# LED_7SEG.net
KiCad netlist of a schematic drawn in Altium Designer
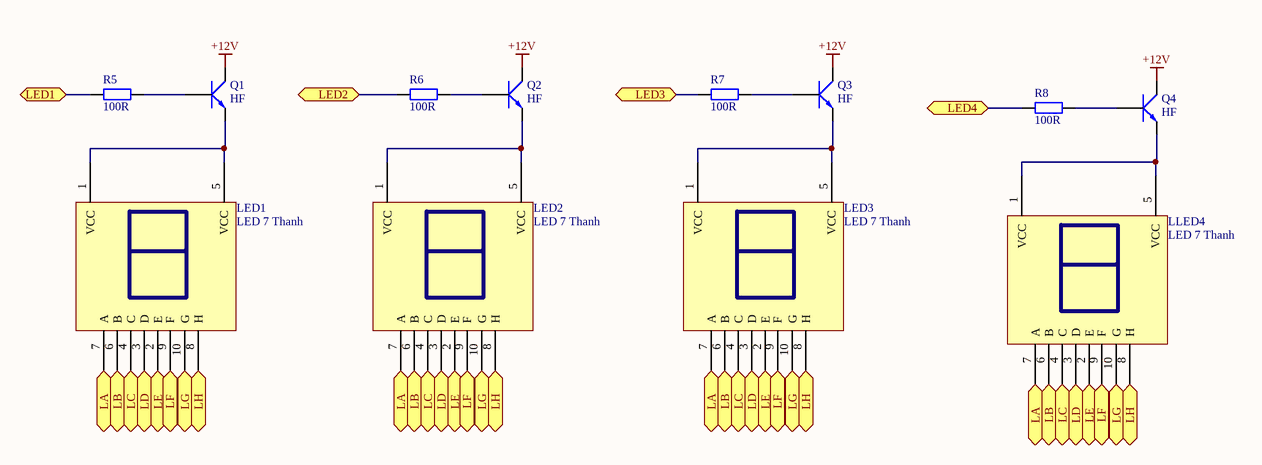
[diagram p0: LED_7SEG.SchDoc]

(export (version "E")
  (design (tool "Eeschema 10.0.6"))
  (components
    (comp (ref "LED1")
      (value "LED 7 Thanh")
      (footprint "LED7SEG_2.3inch")
      (description "Dán")
      (libsource (lib "Altium_Lib_by_KhueNguyenCreator") (part "LED 7x1 2.3inch Anot"))
    )
    (comp (ref "LED2")
      (value "LED 7 Thanh")
      (footprint "LED7SEG_2.3inch")
      (description "Dán")
      (libsource (lib "Altium_Lib_by_KhueNguyenCreator") (part "LED 7x1 2.3inch Anot"))
    )
    (comp (ref "LED3")
      (value "LED 7 Thanh")
      (footprint "LED7SEG_2.3inch")
      (description "Dán")
      (libsource (lib "Altium_Lib_by_KhueNguyenCreator") (part "LED 7x1 2.3inch Anot"))
    )
    (comp (ref "LLED4")
      (value "LED 7 Thanh")
      (footprint "LED7SEG_2.3inch")
      (description "Dán")
      (libsource (lib "Altium_Lib_by_KhueNguyenCreator") (part "LED 7x1 2.3inch Anot"))
    )
    (comp (ref "Q1")
      (value "HF")
      (footprint "SOT23")
      (description "NPN transistor")
      (libsource (lib "Altium_Lib_by_KhueNguyenCreator") (part "C1815 HF SMD"))
    )
    (comp (ref "Q2")
      (value "HF")
      (footprint "SOT23")
      (description "NPN transistor")
      (libsource (lib "Altium_Lib_by_KhueNguyenCreator") (part "C1815 HF SMD"))
    )
    (comp (ref "Q3")
      (value "HF")
      (footprint "SOT23")
      (description "NPN transistor")
      (libsource (lib "Altium_Lib_by_KhueNguyenCreator") (part "C1815 HF SMD"))
    )
    (comp (ref "Q4")
      (value "HF")
      (footprint "SOT23")
      (description "NPN transistor")
      (libsource (lib "Altium_Lib_by_KhueNguyenCreator") (part "C1815 HF SMD"))
    )
    (comp (ref "R5")
      (value "100R")
      (footprint "tro smd 0603")
      (description "Dán")
      (libsource (lib "Altium_Lib_by_KhueNguyenCreator") (part "Tro 0603 5% 100R"))
    )
    (comp (ref "R6")
      (value "100R")
      (footprint "tro smd 0603")
      (description "Dán")
      (libsource (lib "Altium_Lib_by_KhueNguyenCreator") (part "Tro 0603 5% 100R"))
    )
    (comp (ref "R7")
      (value "100R")
      (footprint "tro smd 0603")
      (description "Dán")
      (libsource (lib "Altium_Lib_by_KhueNguyenCreator") (part "Tro 0603 5% 100R"))
    )
    (comp (ref "R8")
      (value "100R")
      (footprint "tro smd 0603")
      (description "Dán")
      (libsource (lib "Altium_Lib_by_KhueNguyenCreator") (part "Tro 0603 5% 100R"))
    )
  )
  (nets
    (net (code "1") (name "+12V") (class "Default")
      (node (ref "Q1") (pin "3") (pinfunction "C_3") (pintype "passive"))
      (node (ref "Q2") (pin "3") (pinfunction "C_3") (pintype "passive"))
      (node (ref "Q3") (pin "3") (pinfunction "C_3") (pintype "passive"))
      (node (ref "Q4") (pin "3") (pinfunction "C_3") (pintype "passive"))
    )
    (net (code "2") (name "/LA") (class "Default")
      (node (ref "LED1") (pin "7") (pinfunction "A_7") (pintype "passive"))
      (node (ref "LED2") (pin "7") (pinfunction "A_7") (pintype "passive"))
      (node (ref "LED3") (pin "7") (pinfunction "A_7") (pintype "passive"))
      (node (ref "LLED4") (pin "7") (pinfunction "A_7") (pintype "passive"))
    )
    (net (code "3") (name "/LB") (class "Default")
      (node (ref "LED1") (pin "6") (pinfunction "B_6") (pintype "passive"))
      (node (ref "LED2") (pin "6") (pinfunction "B_6") (pintype "passive"))
      (node (ref "LED3") (pin "6") (pinfunction "B_6") (pintype "passive"))
      (node (ref "LLED4") (pin "6") (pinfunction "B_6") (pintype "passive"))
    )
    (net (code "4") (name "/LC") (class "Default")
      (node (ref "LED1") (pin "4") (pinfunction "C_4") (pintype "passive"))
      (node (ref "LED2") (pin "4") (pinfunction "C_4") (pintype "passive"))
      (node (ref "LED3") (pin "4") (pinfunction "C_4") (pintype "passive"))
      (node (ref "LLED4") (pin "4") (pinfunction "C_4") (pintype "passive"))
    )
    (net (code "5") (name "/LD") (class "Default")
      (node (ref "LED1") (pin "3") (pinfunction "D_3") (pintype "passive"))
      (node (ref "LED2") (pin "3") (pinfunction "D_3") (pintype "passive"))
      (node (ref "LED3") (pin "3") (pinfunction "D_3") (pintype "passive"))
      (node (ref "LLED4") (pin "3") (pinfunction "D_3") (pintype "passive"))
    )
    (net (code "6") (name "/LE") (class "Default")
      (node (ref "LED1") (pin "2") (pinfunction "E_2") (pintype "passive"))
      (node (ref "LED2") (pin "2") (pinfunction "E_2") (pintype "passive"))
      (node (ref "LED3") (pin "2") (pinfunction "E_2") (pintype "passive"))
      (node (ref "LLED4") (pin "2") (pinfunction "E_2") (pintype "passive"))
    )
    (net (code "7") (name "/LED1") (class "Default")
      (node (ref "R5") (pin "1") (pinfunction "1_1") (pintype "passive"))
    )
    (net (code "8") (name "/LED2") (class "Default")
      (node (ref "R6") (pin "1") (pinfunction "1_1") (pintype "passive"))
    )
    (net (code "9") (name "/LED3") (class "Default")
      (node (ref "R7") (pin "1") (pinfunction "1_1") (pintype "passive"))
    )
    (net (code "10") (name "/LED4") (class "Default")
      (node (ref "R8") (pin "1") (pinfunction "1_1") (pintype "passive"))
    )
    (net (code "11") (name "/LF") (class "Default")
      (node (ref "LED1") (pin "9") (pinfunction "F_9") (pintype "passive"))
      (node (ref "LED2") (pin "9") (pinfunction "F_9") (pintype "passive"))
      (node (ref "LED3") (pin "9") (pinfunction "F_9") (pintype "passive"))
      (node (ref "LLED4") (pin "9") (pinfunction "F_9") (pintype "passive"))
    )
    (net (code "12") (name "/LG") (class "Default")
      (node (ref "LED1") (pin "10") (pinfunction "G_10") (pintype "passive"))
      (node (ref "LED2") (pin "10") (pinfunction "G_10") (pintype "passive"))
      (node (ref "LED3") (pin "10") (pinfunction "G_10") (pintype "passive"))
      (node (ref "LLED4") (pin "10") (pinfunction "G_10") (pintype "passive"))
    )
    (net (code "13") (name "/LH") (class "Default")
      (node (ref "LED1") (pin "8") (pinfunction "H_8") (pintype "passive"))
      (node (ref "LED2") (pin "8") (pinfunction "H_8") (pintype "passive"))
      (node (ref "LED3") (pin "8") (pinfunction "H_8") (pintype "passive"))
      (node (ref "LLED4") (pin "8") (pinfunction "H_8") (pintype "passive"))
    )
    (net (code "14") (name "Net-(Q1-B)") (class "Default")
      (node (ref "Q1") (pin "1") (pinfunction "B_1") (pintype "passive"))
      (node (ref "R5") (pin "2") (pinfunction "2_2") (pintype "passive"))
    )
    (net (code "15") (name "Net-(Q1-E)") (class "Default")
      (node (ref "LED1") (pin "1") (pinfunction "VCC_1") (pintype "passive"))
      (node (ref "LED1") (pin "5") (pinfunction "VCC_5") (pintype "passive"))
      (node (ref "Q1") (pin "2") (pinfunction "E_2") (pintype "passive"))
    )
    (net (code "16") (name "Net-(Q2-B)") (class "Default")
      (node (ref "Q2") (pin "1") (pinfunction "B_1") (pintype "passive"))
      (node (ref "R6") (pin "2") (pinfunction "2_2") (pintype "passive"))
    )
    (net (code "17") (name "Net-(Q2-E)") (class "Default")
      (node (ref "LED2") (pin "1") (pinfunction "VCC_1") (pintype "passive"))
      (node (ref "LED2") (pin "5") (pinfunction "VCC_5") (pintype "passive"))
      (node (ref "Q2") (pin "2") (pinfunction "E_2") (pintype "passive"))
    )
    (net (code "18") (name "Net-(Q3-B)") (class "Default")
      (node (ref "Q3") (pin "1") (pinfunction "B_1") (pintype "passive"))
      (node (ref "R7") (pin "2") (pinfunction "2_2") (pintype "passive"))
    )
    (net (code "19") (name "Net-(Q3-E)") (class "Default")
      (node (ref "LED3") (pin "1") (pinfunction "VCC_1") (pintype "passive"))
      (node (ref "LED3") (pin "5") (pinfunction "VCC_5") (pintype "passive"))
      (node (ref "Q3") (pin "2") (pinfunction "E_2") (pintype "passive"))
    )
    (net (code "20") (name "Net-(Q4-B)") (class "Default")
      (node (ref "Q4") (pin "1") (pinfunction "B_1") (pintype "passive"))
      (node (ref "R8") (pin "2") (pinfunction "2_2") (pintype "passive"))
    )
    (net (code "21") (name "Net-(Q4-E)") (class "Default")
      (node (ref "LLED4") (pin "1") (pinfunction "VCC_1") (pintype "passive"))
      (node (ref "LLED4") (pin "5") (pinfunction "VCC_5") (pintype "passive"))
      (node (ref "Q4") (pin "2") (pinfunction "E_2") (pintype "passive"))
    )
  )
)
